# WZ4827R043-ESP32-V1_1-20230705.net
KiCad netlist of a schematic drawn in EAGLE
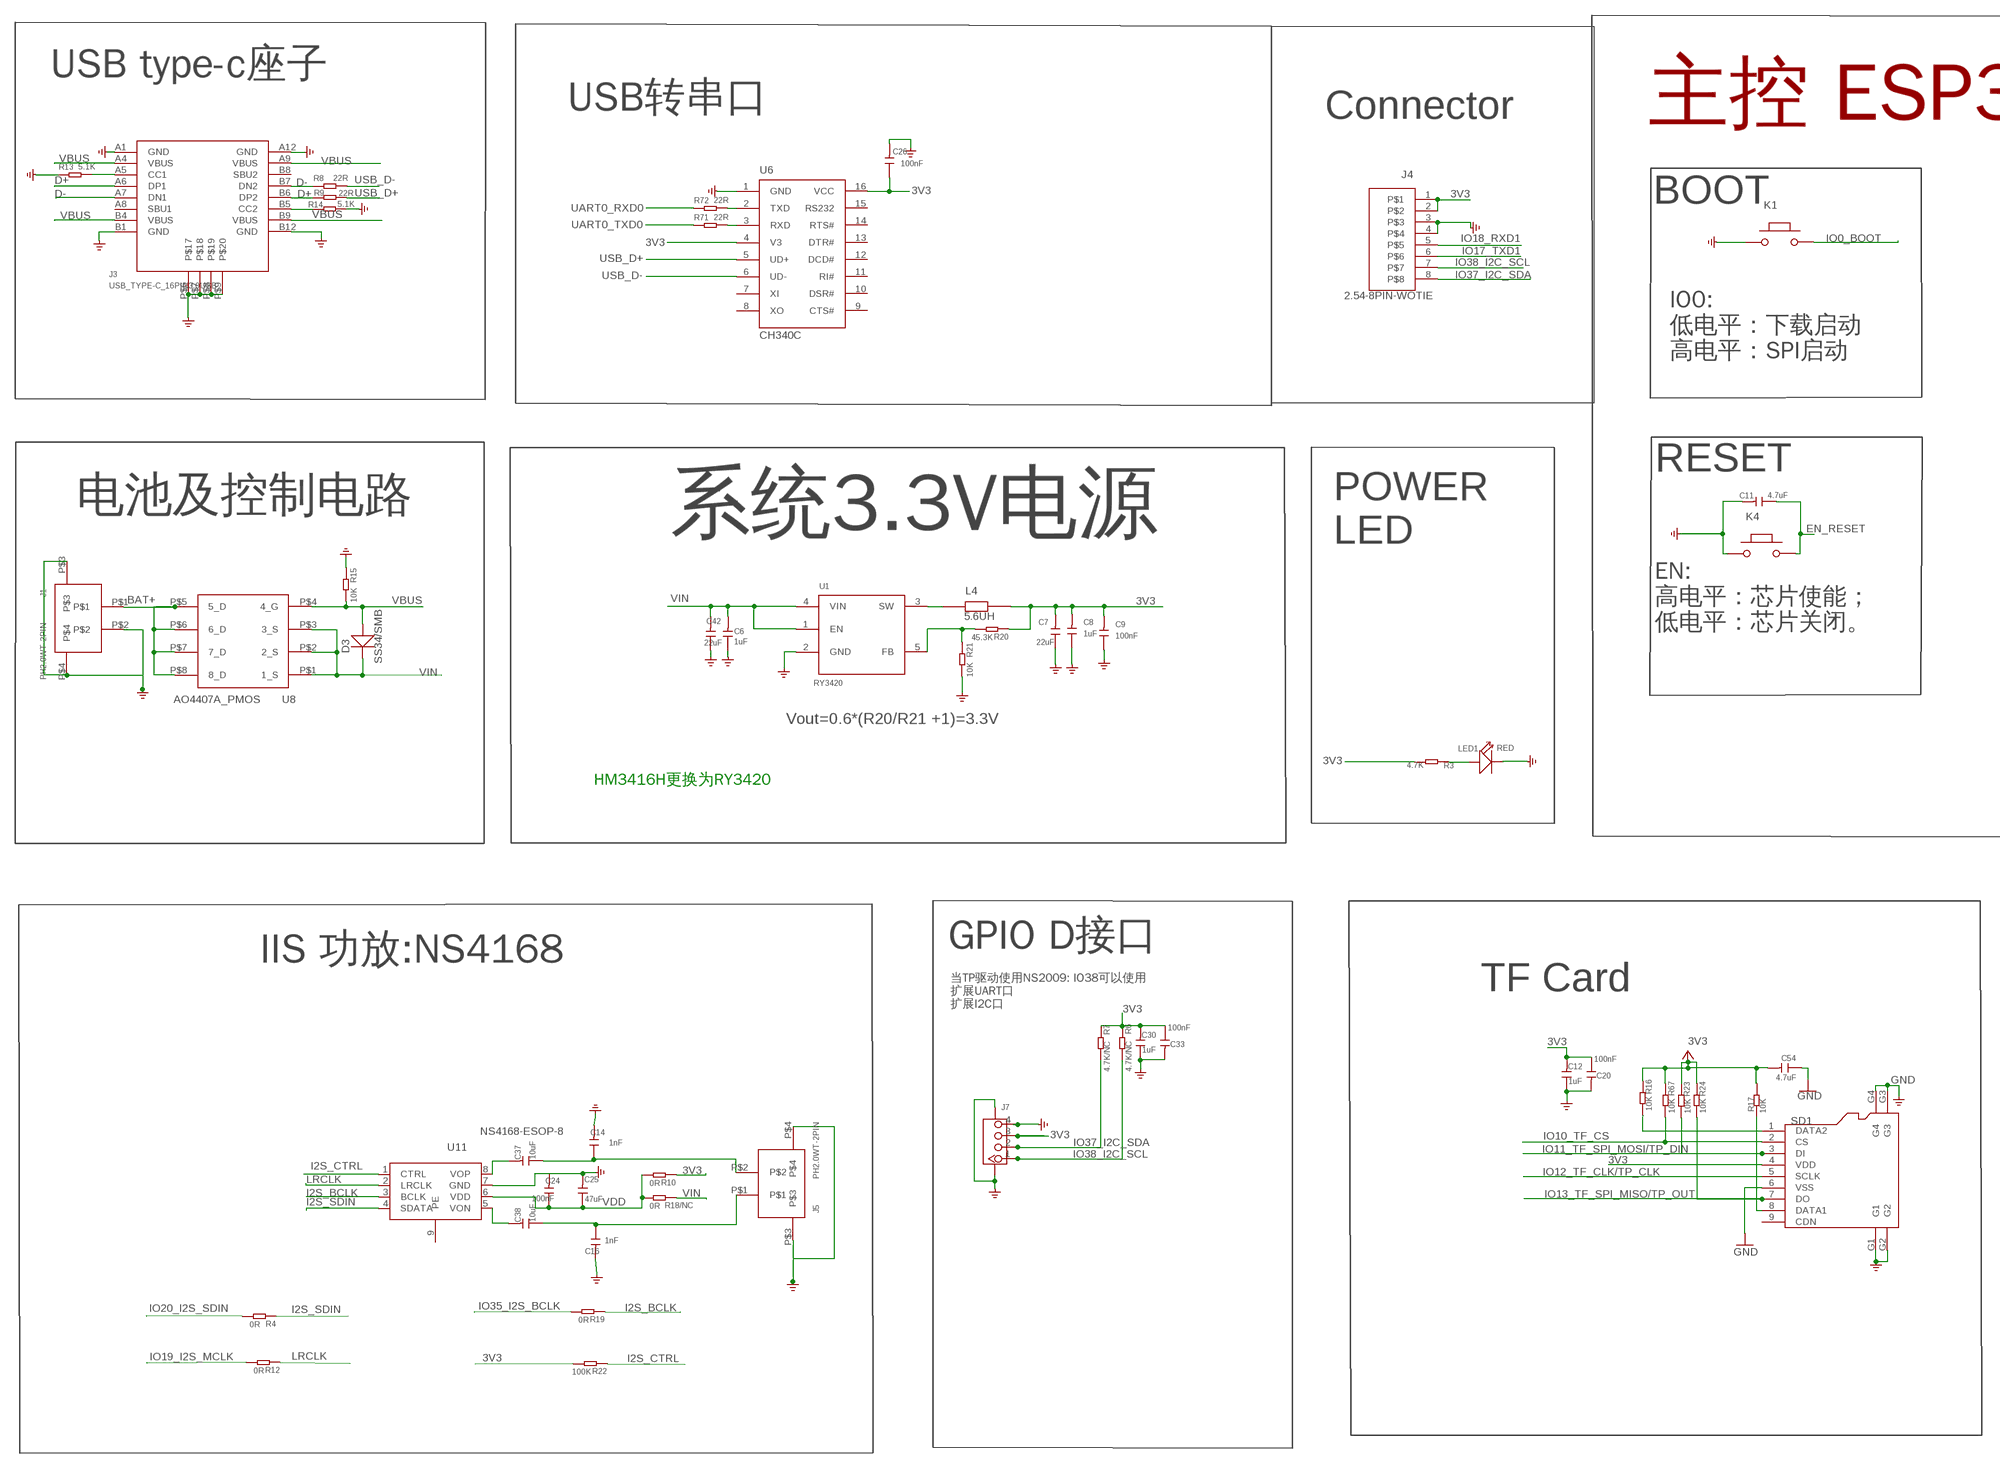
[diagram p0: schematic, sheet 1, part 1 of 2]
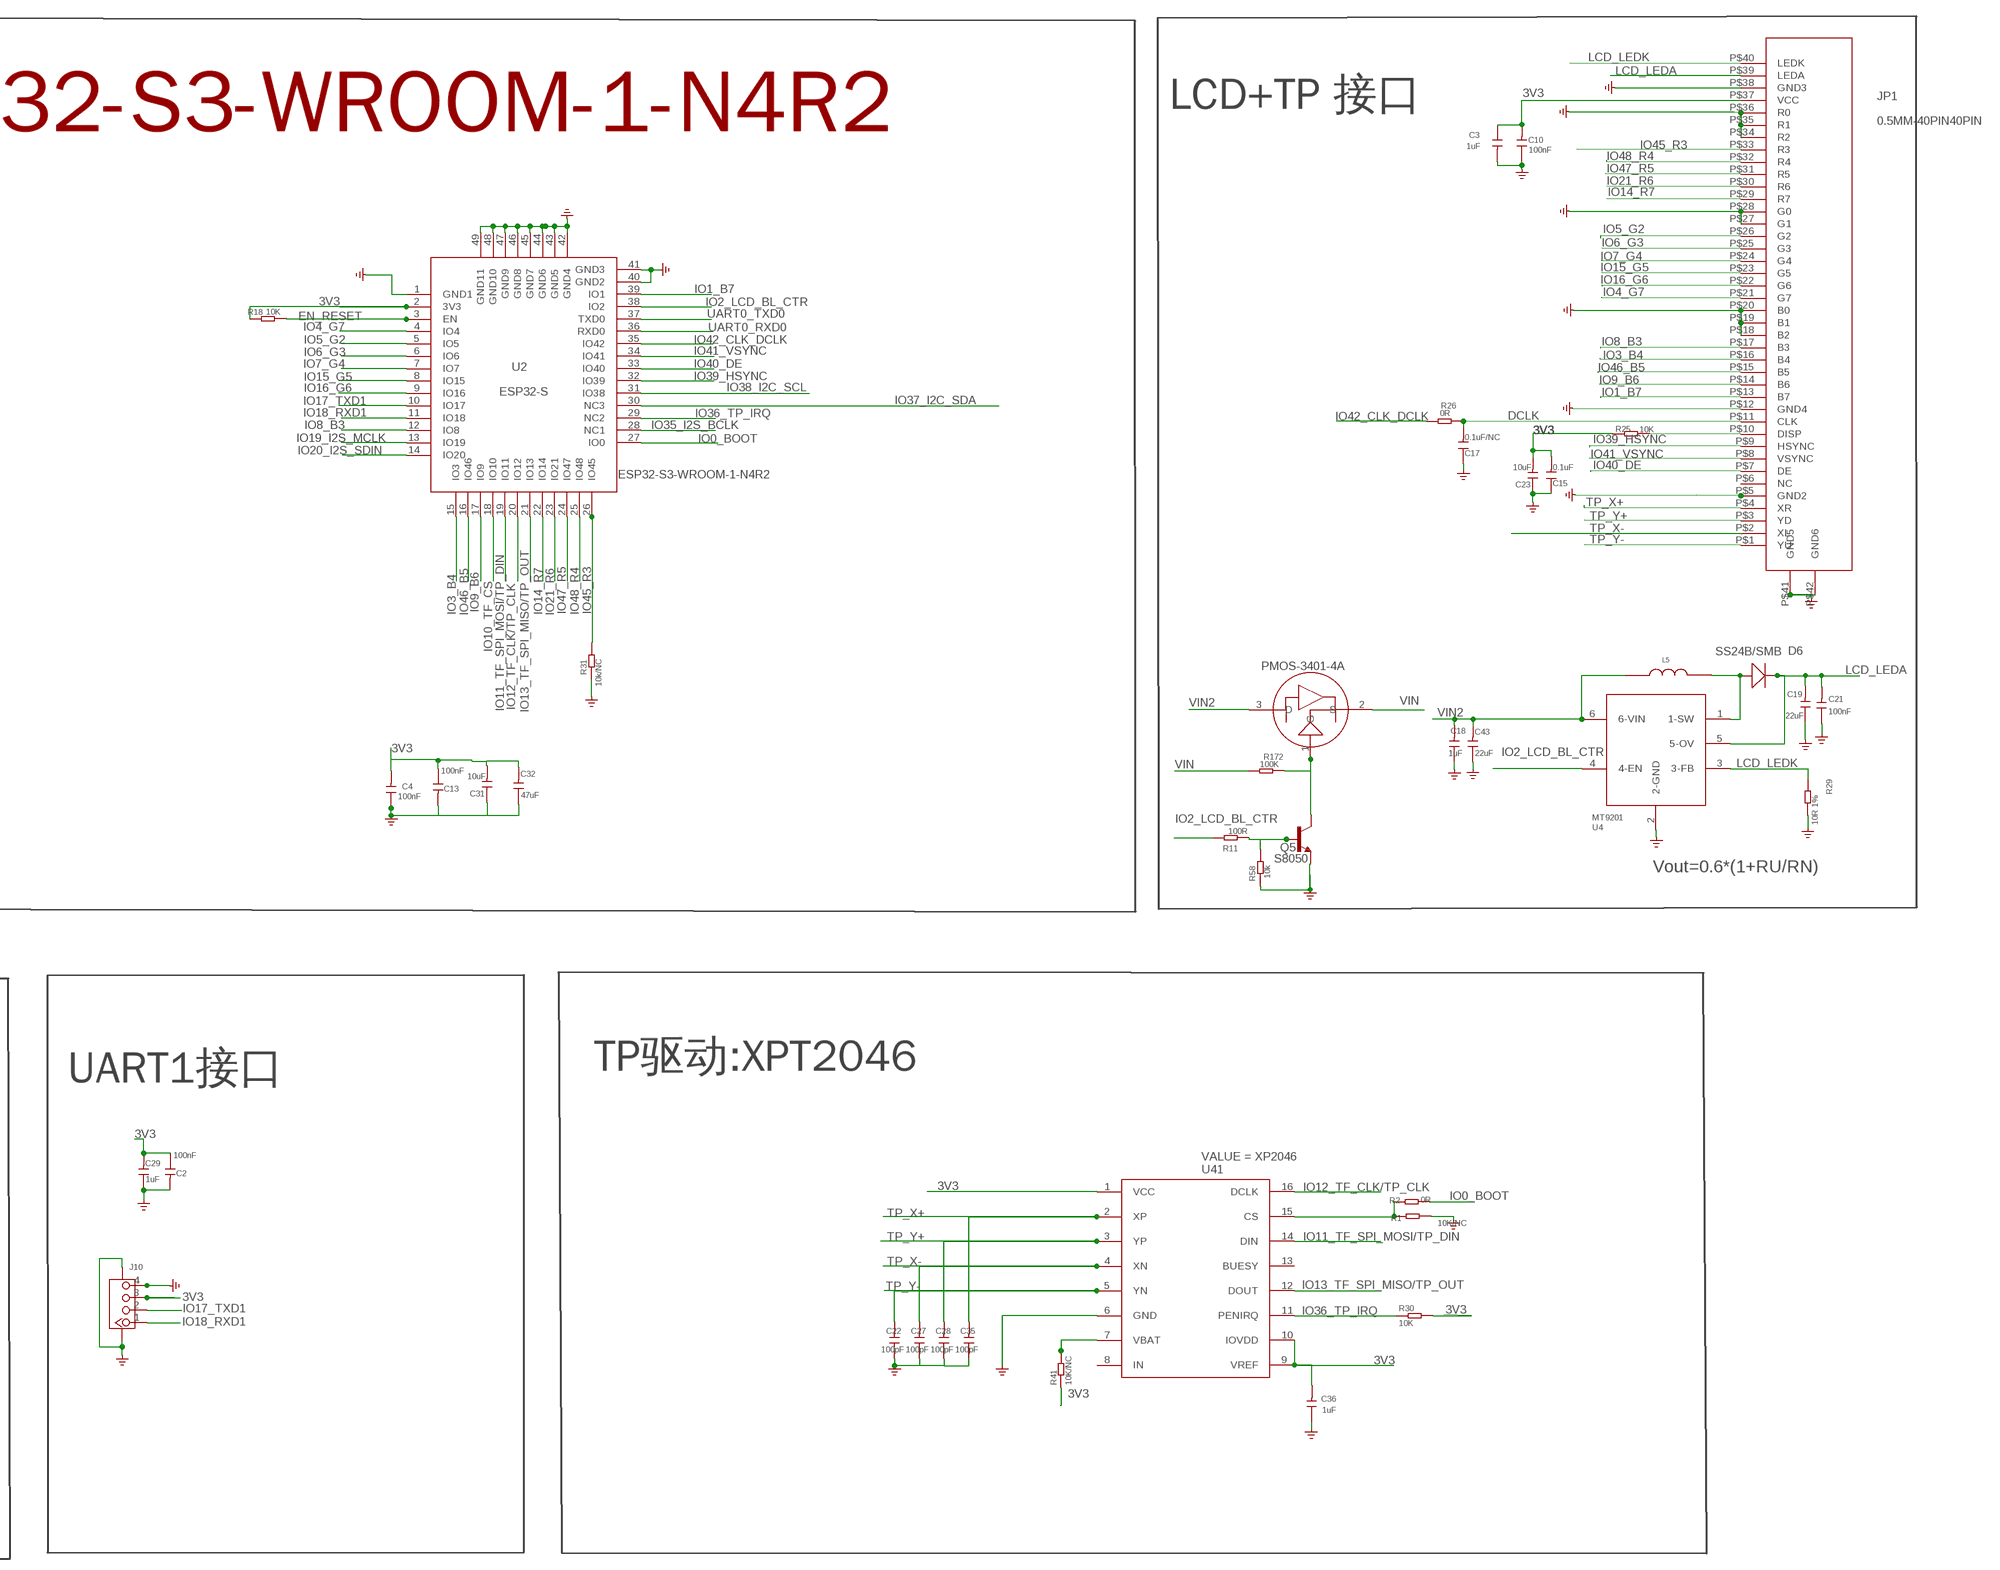
[diagram p1: schematic, sheet 1, part 2 of 2]

(export (version "E")
  (design (tool "Eeschema 10.0.6"))
  (components
    (comp (ref "C2")
      (value "100nF")
      (footprint "eagle-import:C0603")
      (libsource (lib "eagle-import") (part "C-0603"))
    )
    (comp (ref "C3")
      (value "1uF")
      (footprint "eagle-import:C0603")
      (libsource (lib "eagle-import") (part "C-0603"))
    )
    (comp (ref "C4")
      (value "100nF")
      (footprint "eagle-import:C0603")
      (libsource (lib "eagle-import") (part "C-0603"))
    )
    (comp (ref "C6")
      (value "1uF")
      (footprint "eagle-import:0603")
      (libsource (lib "eagle-import") (part "C0603"))
    )
    (comp (ref "C7")
      (value "22uF")
      (footprint "eagle-import:0805")
      (libsource (lib "eagle-import") (part "C0805"))
    )
    (comp (ref "C8")
      (value "1uF")
      (footprint "eagle-import:0603")
      (libsource (lib "eagle-import") (part "C0603"))
    )
    (comp (ref "C9")
      (value "100nF")
      (footprint "eagle-import:0603")
      (libsource (lib "eagle-import") (part "C0603"))
    )
    (comp (ref "C10")
      (value "100nF")
      (footprint "eagle-import:C0603")
      (libsource (lib "eagle-import") (part "C-0603"))
    )
    (comp (ref "C11")
      (value "4.7uF")
      (footprint "eagle-import:0603")
      (libsource (lib "eagle-import") (part "C0603"))
    )
    (comp (ref "C12")
      (value "1uF")
      (footprint "eagle-import:DISCRETE_C0603")
      (libsource (lib "eagle-import") (part "A_xbj_DISCRETE_C-0603"))
    )
    (comp (ref "C13")
      (value "100nF")
      (footprint "eagle-import:C0603")
      (libsource (lib "eagle-import") (part "C-0603"))
    )
    (comp (ref "C14")
      (value "1nF")
      (footprint "eagle-import:C0603")
      (libsource (lib "eagle-import") (part "C-0603"))
    )
    (comp (ref "C15")
      (value "0.1uF")
      (footprint "eagle-import:DISCRETE_C0603")
      (libsource (lib "eagle-import") (part "DISCRETE_C-0603"))
    )
    (comp (ref "C16")
      (value "1nF")
      (footprint "eagle-import:C0603")
      (libsource (lib "eagle-import") (part "C-0603"))
    )
    (comp (ref "C17")
      (value "0.1uF/NC")
      (footprint "eagle-import:DISCRETE_C0603")
      (libsource (lib "eagle-import") (part "DISCRETE_C-0603"))
    )
    (comp (ref "C18")
      (value "1uF")
      (footprint "eagle-import:0603")
      (libsource (lib "eagle-import") (part "C0603"))
    )
    (comp (ref "C19")
      (value "22uF")
      (footprint "eagle-import:0805")
      (libsource (lib "eagle-import") (part "C0805"))
    )
    (comp (ref "C20")
      (value "100nF")
      (footprint "eagle-import:C0603")
      (libsource (lib "eagle-import") (part "C-0603"))
    )
    (comp (ref "C21")
      (value "100nF")
      (footprint "eagle-import:0603")
      (libsource (lib "eagle-import") (part "C0603"))
    )
    (comp (ref "C22")
      (value "100pF")
      (footprint "eagle-import:0603")
      (libsource (lib "eagle-import") (part "C0603"))
    )
    (comp (ref "C23")
      (value "10uF")
      (footprint "eagle-import:DISCRETE_C0603")
      (libsource (lib "eagle-import") (part "DISCRETE_C-0603"))
    )
    (comp (ref "C24")
      (value "100nF")
      (footprint "eagle-import:C0603")
      (libsource (lib "eagle-import") (part "C-0603"))
    )
    (comp (ref "C25")
      (value "47uF")
      (footprint "eagle-import:0805")
      (libsource (lib "eagle-import") (part "C0805"))
    )
    (comp (ref "C26")
      (value "100nF")
      (footprint "eagle-import:0603")
      (libsource (lib "eagle-import") (part "C0603"))
    )
    (comp (ref "C27")
      (value "100pF")
      (footprint "eagle-import:0603")
      (libsource (lib "eagle-import") (part "C0603"))
    )
    (comp (ref "C28")
      (value "100pF")
      (footprint "eagle-import:0603")
      (libsource (lib "eagle-import") (part "C0603"))
    )
    (comp (ref "C29")
      (value "1uF")
      (footprint "eagle-import:DISCRETE_C0603")
      (libsource (lib "eagle-import") (part "A_xbj_DISCRETE_C-0603"))
    )
    (comp (ref "C30")
      (value "1uF")
      (footprint "eagle-import:DISCRETE_C0603")
      (libsource (lib "eagle-import") (part "A_xbj_DISCRETE_C-0603"))
    )
    (comp (ref "C31")
      (value "10uF")
      (footprint "eagle-import:DISCRETE_C0603")
      (libsource (lib "eagle-import") (part "DISCRETE_C-0603"))
    )
    (comp (ref "C32")
      (value "47uF")
      (footprint "eagle-import:0805")
      (libsource (lib "eagle-import") (part "C0805"))
    )
    (comp (ref "C33")
      (value "100nF")
      (footprint "eagle-import:C0603")
      (libsource (lib "eagle-import") (part "C-0603"))
    )
    (comp (ref "C35")
      (value "100pF")
      (footprint "eagle-import:0603")
      (libsource (lib "eagle-import") (part "C0603"))
    )
    (comp (ref "C36")
      (value "1uF")
      (footprint "eagle-import:DISCRETE_C0603")
      (libsource (lib "eagle-import") (part "A_xbj_DISCRETE_C-0603"))
    )
    (comp (ref "C37")
      (value "10uF")
      (footprint "eagle-import:DISCRETE_C0603")
      (libsource (lib "eagle-import") (part "A_xbj_DISCRETE_C-0603"))
    )
    (comp (ref "C38")
      (value "10uF")
      (footprint "eagle-import:DISCRETE_C0603")
      (libsource (lib "eagle-import") (part "A_xbj_DISCRETE_C-0603"))
    )
    (comp (ref "C42")
      (value "22uF")
      (footprint "eagle-import:0805")
      (libsource (lib "eagle-import") (part "C0805"))
    )
    (comp (ref "C43")
      (value "22uF")
      (footprint "eagle-import:0805")
      (libsource (lib "eagle-import") (part "C0805"))
    )
    (comp (ref "C54")
      (value "4.7uF")
      (footprint "eagle-import:DISCRETE_C0603")
      (libsource (lib "eagle-import") (part "DISCRETE_C-0603"))
    )
    (comp (ref "D3")
      (value "SS34/SMB")
      (footprint "eagle-import:214AB")
      (libsource (lib "eagle-import") (part "214ABDO-214AB"))
    )
    (comp (ref "D6")
      (value "SS24B/SMB")
      (footprint "eagle-import:214AB")
      (libsource (lib "eagle-import") (part "214ABDO-214AB"))
    )
    (comp (ref "J1")
      (value "PH2.0WT-2PIN")
      (footprint "eagle-import:PH2.0WT-2PIN")
      (libsource (lib "eagle-import") (part "PH2.0WT-2PIN"))
    )
    (comp (ref "J3")
      (value "USB_TYPE-C_16PIN3.0USB")
      (footprint "eagle-import:KEVIN_3.0TYPEC-SMD")
      (libsource (lib "eagle-import") (part "USB_TYPE-C_16PIN3.0USB"))
    )
    (comp (ref "J4")
      (value "2.54-8PIN-WOTIE")
      (footprint "eagle-import:2.54-8P-WOTIE")
      (libsource (lib "eagle-import") (part "2.54-8PIN-WOTIE"))
    )
    (comp (ref "J5")
      (value "PH2.0WT-2PIN")
      (footprint "eagle-import:PH2.0WT-2PIN")
      (libsource (lib "eagle-import") (part "PH2.0WT-2PIN"))
    )
    (comp (ref "J7")
      (value "CONNECTOR_TWIG-4P-2.0-SMD-FEMALE-REINFORCE90D")
      (footprint "eagle-import:CONNECTOR_4P-SMD-2.0-90D")
      (libsource (lib "eagle-import") (part "CONNECTOR_TWIG-4P-2.0-SMD-FEMALE-REINFORCE90D"))
    )
    (comp (ref "J10")
      (value "CONNECTOR_TWIG-4P-2.0-SMD-FEMALE-REINFORCE90D")
      (footprint "eagle-import:CONNECTOR_4P-SMD-2.0-90D")
      (libsource (lib "eagle-import") (part "CONNECTOR_TWIG-4P-2.0-SMD-FEMALE-REINFORCE90D"))
    )
    (comp (ref "JP1")
      (value "0.5MM-40PIN40PIN")
      (footprint "eagle-import:0.5MM_40P")
      (libsource (lib "eagle-import") (part "0.5MM-40PIN40PIN"))
    )
    (comp (ref "K1")
      (value "BUTTON")
      (footprint "eagle-import:157SW")
      (libsource (lib "eagle-import") (part "PB157"))
    )
    (comp (ref "K4")
      (value "BUTTON")
      (footprint "eagle-import:157SW")
      (libsource (lib "eagle-import") (part "PB157"))
    )
    (comp (ref "L4")
      (value "5.6UH")
      (footprint "eagle-import:CD54")
      (libsource (lib "eagle-import") (part "CROWPI2-MB-V1.4-20211012_CMP201209UD1R0MT"))
    )
    (comp (ref "L5")
      (value "CD32_6.8uH")
      (footprint "eagle-import:CD32")
      (libsource (lib "eagle-import") (part "CD32_950MA"))
    )
    (comp (ref "LED1")
      (value "RED")
      (footprint "eagle-import:DISCRETE_LED-0603")
      (libsource (lib "eagle-import") (part "DISCRETE_LED0603"))
    )
    (comp (ref "Q5")
      (value "S8050")
      (footprint "eagle-import:SPARKFUN_SOT23")
      (libsource (lib "eagle-import") (part "SPARKFUN_TRANSISTOR_NPNSOT23"))
    )
    (comp (ref "Q30")
      (value "PMOS-3401-4A")
      (footprint "eagle-import:SOT-23")
      (libsource (lib "eagle-import") (part "P-MOS-SOT23"))
    )
    (comp (ref "R1")
      (value "10K/NC")
      (footprint "eagle-import:R0603")
      (libsource (lib "eagle-import") (part "R0603"))
    )
    (comp (ref "R2")
      (value "0R")
      (footprint "eagle-import:DISCRETE_R0603")
      (libsource (lib "eagle-import") (part "Crowtail-_LED-V2.0-20190615-01_DISCRETE_R-0603"))
    )
    (comp (ref "R3")
      (value "4.7K")
      (footprint "eagle-import:DISCRETE_R0603")
      (libsource (lib "eagle-import") (part "Crowtail-_LED-V2.0-20190615-01_DISCRETE_R-0603"))
    )
    (comp (ref "R4")
      (value "0R")
      (footprint "eagle-import:DISCRETE_R0603")
      (libsource (lib "eagle-import") (part "Crowtail-_LED-V2.0-20190615-01_DISCRETE_R-0603"))
    )
    (comp (ref "R6")
      (value "4.7K/NC")
      (footprint "eagle-import:DISCRETE_R0603")
      (libsource (lib "eagle-import") (part "Crowtail-_LED-V2.0-20190615-01_DISCRETE_R-0603"))
    )
    (comp (ref "R7")
      (value "4.7K/NC")
      (footprint "eagle-import:DISCRETE_R0603")
      (libsource (lib "eagle-import") (part "Crowtail-_LED-V2.0-20190615-01_DISCRETE_R-0603"))
    )
    (comp (ref "R8")
      (value "22R")
      (footprint "eagle-import:DISCRETE_R0603")
      (libsource (lib "eagle-import") (part "Crowtail-_LED-V2.0-20190615-01_DISCRETE_R-0603"))
    )
    (comp (ref "R9")
      (value "22R")
      (footprint "eagle-import:DISCRETE_R0603")
      (libsource (lib "eagle-import") (part "Crowtail-_LED-V2.0-20190615-01_DISCRETE_R-0603"))
    )
    (comp (ref "R10")
      (value "0R")
      (footprint "eagle-import:DISCRETE_R0603")
      (libsource (lib "eagle-import") (part "Crowtail-_LED-V2.0-20190615-01_DISCRETE_R-0603"))
    )
    (comp (ref "R11")
      (value "100R")
      (footprint "eagle-import:R0603")
      (libsource (lib "eagle-import") (part "R0603"))
    )
    (comp (ref "R12")
      (value "0R")
      (footprint "eagle-import:DISCRETE_R0603")
      (libsource (lib "eagle-import") (part "Crowtail-_LED-V2.0-20190615-01_DISCRETE_R-0603"))
    )
    (comp (ref "R13")
      (value "5.1K")
      (footprint "eagle-import:DISCRETE_R0603")
      (libsource (lib "eagle-import") (part "Crowtail-_LED-V2.0-20190615-01_DISCRETE_R-0603"))
    )
    (comp (ref "R14")
      (value "5.1K")
      (footprint "eagle-import:DISCRETE_R0603")
      (libsource (lib "eagle-import") (part "Crowtail-_LED-V2.0-20190615-01_DISCRETE_R-0603"))
    )
    (comp (ref "R15")
      (value "10K")
      (footprint "eagle-import:DISCRETE_R0603")
      (libsource (lib "eagle-import") (part "Crowtail-_LED-V2.0-20190615-01_DISCRETE_R-0603"))
    )
    (comp (ref "R16")
      (value "10K")
      (footprint "eagle-import:DISCRETE_R0603")
      (libsource (lib "eagle-import") (part "Crowtail-_LED-V2.0-20190615-01_DISCRETE_R-0603"))
    )
    (comp (ref "R17")
      (value "10K")
      (footprint "eagle-import:DISCRETE_R0603")
      (libsource (lib "eagle-import") (part "Crowtail-_LED-V2.0-20190615-01_DISCRETE_R-0603"))
    )
    (comp (ref "R18")
      (value "10K")
      (footprint "eagle-import:DISCRETE_R0603")
      (libsource (lib "eagle-import") (part "Crowtail-_LED-V2.0-20190615-01_DISCRETE_R-0603"))
    )
    (comp (ref "R18/NC")
      (value "0R")
      (footprint "eagle-import:DISCRETE_R0603")
      (libsource (lib "eagle-import") (part "Crowtail-_LED-V2.0-20190615-01_DISCRETE_R-0603"))
    )
    (comp (ref "R19")
      (value "0R")
      (footprint "eagle-import:DISCRETE_R0603")
      (libsource (lib "eagle-import") (part "Crowtail-_LED-V2.0-20190615-01_DISCRETE_R-0603"))
    )
    (comp (ref "R20")
      (value "45.3K")
      (footprint "eagle-import:DISCRETE_R0603")
      (libsource (lib "eagle-import") (part "Crowtail-_LED-V2.0-20190615-01_DISCRETE_R-0603"))
    )
    (comp (ref "R21")
      (value "10K")
      (footprint "eagle-import:DISCRETE_R0603")
      (libsource (lib "eagle-import") (part "Crowtail-_LED-V2.0-20190615-01_DISCRETE_R-0603"))
    )
    (comp (ref "R22")
      (value "100K")
      (footprint "eagle-import:DISCRETE_R0603")
      (libsource (lib "eagle-import") (part "Crowtail-_LED-V2.0-20190615-01_DISCRETE_R-0603"))
    )
    (comp (ref "R23")
      (value "10K")
      (footprint "eagle-import:DISCRETE_R0603")
      (libsource (lib "eagle-import") (part "Crowtail-_LED-V2.0-20190615-01_DISCRETE_R-0603"))
    )
    (comp (ref "R24")
      (value "10K")
      (footprint "eagle-import:DISCRETE_R0603")
      (libsource (lib "eagle-import") (part "Crowtail-_LED-V2.0-20190615-01_DISCRETE_R-0603"))
    )
    (comp (ref "R25")
      (value "10K")
      (footprint "eagle-import:DISCRETE_R0603")
      (libsource (lib "eagle-import") (part "Crowtail-_LED-V2.0-20190615-01_DISCRETE_R-0603"))
    )
    (comp (ref "R26")
      (value "0R")
      (footprint "eagle-import:R0603")
      (libsource (lib "eagle-import") (part "R-0603"))
    )
    (comp (ref "R29")
      (value "10R 1%")
      (footprint "eagle-import:DISCRETE_R0603")
      (libsource (lib "eagle-import") (part "Crowtail-_LED-V2.0-20190615-01_DISCRETE_R-0603"))
    )
    (comp (ref "R30")
      (value "10K")
      (footprint "eagle-import:DISCRETE_R0603")
      (libsource (lib "eagle-import") (part "DISCRETE_R-0603"))
    )
    (comp (ref "R31")
      (value "10k/NC")
      (footprint "eagle-import:R0603")
      (libsource (lib "eagle-import") (part "R0603"))
    )
    (comp (ref "R41")
      (value "10K/NC")
      (footprint "eagle-import:DISCRETE_R0603")
      (libsource (lib "eagle-import") (part "DISCRETE_R-0603"))
    )
    (comp (ref "R58")
      (value "10k")
      (footprint "eagle-import:R0603")
      (libsource (lib "eagle-import") (part "R0603"))
    )
    (comp (ref "R67")
      (value "10K")
      (footprint "eagle-import:DISCRETE_R0603")
      (libsource (lib "eagle-import") (part "Crowtail-_LED-V2.0-20190615-01_DISCRETE_R-0603"))
    )
    (comp (ref "R71")
      (value "22R")
      (footprint "eagle-import:DISCRETE_R0603")
      (libsource (lib "eagle-import") (part "Crowtail-_LED-V2.0-20190615-01_DISCRETE_R-0603"))
    )
    (comp (ref "R72")
      (value "22R")
      (footprint "eagle-import:DISCRETE_R0603")
      (libsource (lib "eagle-import") (part "Crowtail-_LED-V2.0-20190615-01_DISCRETE_R-0603"))
    )
    (comp (ref "R172")
      (value "100K")
      (footprint "eagle-import:R0603")
      (libsource (lib "eagle-import") (part "R-0603"))
    )
    (comp (ref "SD1")
      (value "HOLDER-MICROSD-9P")
      (footprint "eagle-import:9P-SMD-W_-RING")
      (libsource (lib "eagle-import") (part "HOLDER-MICROSD-9P"))
    )
    (comp (ref "U1")
      (value "RY3420")
      (footprint "eagle-import:A_XBJ_SOT23-5")
      (libsource (lib "eagle-import") (part "A_XBJ_HM3420B"))
    )
    (comp (ref "U2")
      (value "ESP32-S")
      (footprint "eagle-import:ESP32-S3")
      (fields (field (name "U2") "ESP32-S3-WROOM-1-N4R2"))
      (libsource (lib "eagle-import") (part "ESP32-S"))
    )
    (comp (ref "U4")
      (value "MT9201")
      (footprint "eagle-import:SOT23-6")
      (libsource (lib "eagle-import") (part "MT9201"))
    )
    (comp (ref "U6")
      (value "CH340C")
      (footprint "eagle-import:SOP-16")
      (libsource (lib "eagle-import") (part "CH340G"))
    )
    (comp (ref "U8")
      (value "AO4407A_PMOS")
      (footprint "eagle-import:SOP8")
      (libsource (lib "eagle-import") (part "T_PMOS_AO4407A_SOP8"))
    )
    (comp (ref "U11")
      (value "NS4168-ESOP-8")
      (footprint "eagle-import:NS4168-ESOP-8")
      (libsource (lib "eagle-import") (part "NS4168-ESOP-8"))
    )
    (comp (ref "U41")
      (value "XP2046")
      (footprint "eagle-import:XP2046-SSOP16")
      (libsource (lib "eagle-import") (part "XP2046"))
    )
  )
  (nets
    (net (code "1") (name "+3V3") (class "Default")
      (node (ref "C10") (pin "2") (pinfunction "2_2") (pintype "passive"))
      (node (ref "C12") (pin "2") (pinfunction "2_2") (pintype "passive"))
      (node (ref "C13") (pin "1") (pinfunction "1_1") (pintype "passive"))
      (node (ref "C15") (pin "2") (pinfunction "2_2") (pintype "passive"))
      (node (ref "C2") (pin "1") (pinfunction "1_1") (pintype "passive"))
      (node (ref "C20") (pin "1") (pinfunction "1_1") (pintype "passive"))
      (node (ref "C23") (pin "2") (pinfunction "2_2") (pintype "passive"))
      (node (ref "C26") (pin "1") (pinfunction "1_1") (pintype "passive"))
      (node (ref "C29") (pin "2") (pinfunction "2_2") (pintype "passive"))
      (node (ref "C3") (pin "1") (pinfunction "1_1") (pintype "passive"))
      (node (ref "C30") (pin "2") (pinfunction "2_2") (pintype "passive"))
      (node (ref "C31") (pin "2") (pinfunction "2_2") (pintype "passive"))
      (node (ref "C32") (pin "2") (pinfunction "2_2") (pintype "passive"))
      (node (ref "C33") (pin "1") (pinfunction "1_1") (pintype "passive"))
      (node (ref "C36") (pin "2") (pinfunction "2_2") (pintype "passive"))
      (node (ref "C4") (pin "2") (pinfunction "2_2") (pintype "passive"))
      (node (ref "C54") (pin "2") (pinfunction "2_2") (pintype "passive"))
      (node (ref "C7") (pin "2") (pinfunction "2_2") (pintype "passive"))
      (node (ref "C8") (pin "2") (pinfunction "2_2") (pintype "passive"))
      (node (ref "C9") (pin "2") (pinfunction "2_2") (pintype "passive"))
      (node (ref "J10") (pin "3") (pinfunction "3_3") (pintype "bidirectional"))
      (node (ref "J4") (pin "1") (pinfunction "P$1_1") (pintype "bidirectional"))
      (node (ref "J4") (pin "2") (pinfunction "P$2_2") (pintype "bidirectional"))
      (node (ref "J7") (pin "3") (pinfunction "3_3") (pintype "bidirectional"))
      (node (ref "JP1") (pin "P$37") (pinfunction "VCC_P$37") (pintype "bidirectional"))
      (node (ref "L4") (pin "2") (pinfunction "2_2") (pintype "bidirectional"))
      (node (ref "R10") (pin "1") (pinfunction "1_1") (pintype "passive"))
      (node (ref "R16") (pin "1") (pinfunction "1_1") (pintype "passive"))
      (node (ref "R17") (pin "1") (pinfunction "1_1") (pintype "passive"))
      (node (ref "R18") (pin "1") (pinfunction "1_1") (pintype "passive"))
      (node (ref "R20") (pin "1") (pinfunction "1_1") (pintype "passive"))
      (node (ref "R22") (pin "2") (pinfunction "2_2") (pintype "passive"))
      (node (ref "R23") (pin "1") (pinfunction "1_1") (pintype "passive"))
      (node (ref "R24") (pin "1") (pinfunction "1_1") (pintype "passive"))
      (node (ref "R25") (pin "1") (pinfunction "1_1") (pintype "passive"))
      (node (ref "R3") (pin "2") (pinfunction "2_2") (pintype "passive"))
      (node (ref "R30") (pin "2") (pinfunction "2_2") (pintype "passive"))
      (node (ref "R41") (pin "1") (pinfunction "1_1") (pintype "passive"))
      (node (ref "R6") (pin "1") (pinfunction "1_1") (pintype "passive"))
      (node (ref "R67") (pin "1") (pinfunction "1_1") (pintype "passive"))
      (node (ref "R7") (pin "1") (pinfunction "1_1") (pintype "passive"))
      (node (ref "SD1") (pin "4") (pinfunction "VDD_4") (pintype "bidirectional"))
      (node (ref "U2") (pin "2") (pinfunction "3V3_2") (pintype "bidirectional"))
      (node (ref "U41") (pin "1") (pinfunction "VCC_1") (pintype "bidirectional"))
      (node (ref "U41") (pin "10") (pinfunction "IOVDD_10") (pintype "bidirectional"))
      (node (ref "U41") (pin "9") (pinfunction "VREF_9") (pintype "bidirectional"))
      (node (ref "U6") (pin "16") (pinfunction "VCC_16") (pintype "bidirectional"))
      (node (ref "U6") (pin "4") (pinfunction "V3_4") (pintype "bidirectional"))
    )
    (net (code "2") (name "/BAT+") (class "Default")
      (node (ref "J1") (pin "P$1") (pinfunction "P$1_P$1") (pintype "bidirectional"))
      (node (ref "U8") (pin "P$5") (pinfunction "5_D_P$5") (pintype "bidirectional"))
      (node (ref "U8") (pin "P$6") (pinfunction "6_D_P$6") (pintype "bidirectional"))
      (node (ref "U8") (pin "P$7") (pinfunction "7_D_P$7") (pintype "bidirectional"))
      (node (ref "U8") (pin "P$8") (pinfunction "8_D_P$8") (pintype "bidirectional"))
    )
    (net (code "3") (name "/D+") (class "Default")
      (node (ref "J3") (pin "A6") (pinfunction "DP1_A6") (pintype "bidirectional"))
      (node (ref "J3") (pin "B6") (pinfunction "DP2_B6") (pintype "bidirectional"))
      (node (ref "R9") (pin "1") (pinfunction "1_1") (pintype "passive"))
    )
    (net (code "4") (name "/D-") (class "Default")
      (node (ref "J3") (pin "A7") (pinfunction "DN1_A7") (pintype "bidirectional"))
      (node (ref "J3") (pin "B7") (pinfunction "DN2_B7") (pintype "bidirectional"))
      (node (ref "R8") (pin "1") (pinfunction "1_1") (pintype "passive"))
    )
    (net (code "5") (name "/DCLK") (class "Default")
      (node (ref "C17") (pin "2") (pinfunction "2_2") (pintype "passive"))
      (node (ref "JP1") (pin "P$11") (pinfunction "CLK_P$11") (pintype "bidirectional"))
      (node (ref "R26") (pin "2") (pinfunction "2_2") (pintype "passive"))
    )
    (net (code "6") (name "/EN_RESET") (class "Default")
      (node (ref "C11") (pin "1") (pinfunction "1_1") (pintype "passive"))
      (node (ref "K4") (pin "2") (pinfunction "2_2") (pintype "passive"))
      (node (ref "R18") (pin "2") (pinfunction "2_2") (pintype "passive"))
      (node (ref "U2") (pin "3") (pinfunction "EN_3") (pintype "bidirectional"))
    )
    (net (code "7") (name "/I2S_BCLK") (class "Default")
      (node (ref "R19") (pin "1") (pinfunction "1_1") (pintype "passive"))
      (node (ref "U11") (pin "3") (pinfunction "BCLK_3") (pintype "bidirectional"))
    )
    (net (code "8") (name "/I2S_CTRL") (class "Default")
      (node (ref "R22") (pin "1") (pinfunction "1_1") (pintype "passive"))
      (node (ref "U11") (pin "1") (pinfunction "CTRL_1") (pintype "bidirectional"))
    )
    (net (code "9") (name "/I2S_SDIN") (class "Default")
      (node (ref "R4") (pin "1") (pinfunction "1_1") (pintype "passive"))
      (node (ref "U11") (pin "4") (pinfunction "SDATA_4") (pintype "bidirectional"))
    )
    (net (code "10") (name "/IO0_BOOT") (class "Default")
      (node (ref "K1") (pin "2") (pinfunction "2_2") (pintype "passive"))
      (node (ref "R2") (pin "1") (pinfunction "1_1") (pintype "passive"))
      (node (ref "U2") (pin "27") (pinfunction "IO0_27") (pintype "bidirectional"))
    )
    (net (code "11") (name "/IO1_B7") (class "Default")
      (node (ref "JP1") (pin "P$13") (pinfunction "B7_P$13") (pintype "bidirectional"))
      (node (ref "U2") (pin "39") (pinfunction "IO1_39") (pintype "bidirectional"))
    )
    (net (code "12") (name "/IO2_LCD_BL_CTR") (class "Default")
      (node (ref "R11") (pin "2") (pinfunction "2_2") (pintype "passive"))
      (node (ref "U2") (pin "38") (pinfunction "IO2_38") (pintype "bidirectional"))
      (node (ref "U4") (pin "4") (pinfunction "4-EN_4") (pintype "bidirectional"))
    )
    (net (code "13") (name "/IO3_B4") (class "Default")
      (node (ref "JP1") (pin "P$16") (pinfunction "B4_P$16") (pintype "bidirectional"))
      (node (ref "U2") (pin "15") (pinfunction "IO3_15") (pintype "bidirectional"))
    )
    (net (code "14") (name "/IO4_G7") (class "Default")
      (node (ref "JP1") (pin "P$21") (pinfunction "G7_P$21") (pintype "bidirectional"))
      (node (ref "U2") (pin "4") (pinfunction "IO4_4") (pintype "bidirectional"))
    )
    (net (code "15") (name "/IO5_G2") (class "Default")
      (node (ref "JP1") (pin "P$26") (pinfunction "G2_P$26") (pintype "bidirectional"))
      (node (ref "U2") (pin "5") (pinfunction "IO5_5") (pintype "bidirectional"))
    )
    (net (code "16") (name "/IO6_G3") (class "Default")
      (node (ref "JP1") (pin "P$25") (pinfunction "G3_P$25") (pintype "bidirectional"))
      (node (ref "U2") (pin "6") (pinfunction "IO6_6") (pintype "bidirectional"))
    )
    (net (code "17") (name "/IO7_G4") (class "Default")
      (node (ref "JP1") (pin "P$24") (pinfunction "G4_P$24") (pintype "bidirectional"))
      (node (ref "U2") (pin "7") (pinfunction "IO7_7") (pintype "bidirectional"))
    )
    (net (code "18") (name "/IO8_B3") (class "Default")
      (node (ref "JP1") (pin "P$17") (pinfunction "B3_P$17") (pintype "bidirectional"))
      (node (ref "U2") (pin "12") (pinfunction "IO8_12") (pintype "bidirectional"))
    )
    (net (code "19") (name "/IO9_B6") (class "Default")
      (node (ref "JP1") (pin "P$14") (pinfunction "B6_P$14") (pintype "bidirectional"))
      (node (ref "U2") (pin "17") (pinfunction "IO9_17") (pintype "bidirectional"))
    )
    (net (code "20") (name "/IO10_TF_CS") (class "Default")
      (node (ref "R67") (pin "2") (pinfunction "2_2") (pintype "passive"))
      (node (ref "SD1") (pin "2") (pinfunction "CS_2") (pintype "bidirectional"))
      (node (ref "U2") (pin "18") (pinfunction "IO10_18") (pintype "bidirectional"))
    )
    (net (code "21") (name "/IO11_TF_SPI_MOSI{slash}TP_DIN") (class "Default")
      (node (ref "R23") (pin "2") (pinfunction "2_2") (pintype "passive"))
      (node (ref "SD1") (pin "3") (pinfunction "DI_3") (pintype "bidirectional"))
      (node (ref "U2") (pin "19") (pinfunction "IO11_19") (pintype "bidirectional"))
      (node (ref "U41") (pin "14") (pinfunction "DIN_14") (pintype "bidirectional"))
    )
    (net (code "22") (name "/IO12_TF_CLK{slash}TP_CLK") (class "Default")
      (node (ref "SD1") (pin "5") (pinfunction "SCLK_5") (pintype "bidirectional"))
      (node (ref "U2") (pin "20") (pinfunction "IO12_20") (pintype "bidirectional"))
      (node (ref "U41") (pin "16") (pinfunction "DCLK_16") (pintype "bidirectional"))
    )
    (net (code "23") (name "/IO13_TF_SPI_MISO{slash}TP_OUT") (class "Default")
      (node (ref "R24") (pin "2") (pinfunction "2_2") (pintype "passive"))
      (node (ref "SD1") (pin "7") (pinfunction "DO_7") (pintype "bidirectional"))
      (node (ref "U2") (pin "21") (pinfunction "IO13_21") (pintype "bidirectional"))
      (node (ref "U41") (pin "12") (pinfunction "DOUT_12") (pintype "bidirectional"))
    )
    (net (code "24") (name "/IO14_R7") (class "Default")
      (node (ref "JP1") (pin "P$29") (pinfunction "R7_P$29") (pintype "bidirectional"))
      (node (ref "U2") (pin "22") (pinfunction "IO14_22") (pintype "bidirectional"))
    )
    (net (code "25") (name "/IO15_G5") (class "Default")
      (node (ref "JP1") (pin "P$23") (pinfunction "G5_P$23") (pintype "bidirectional"))
      (node (ref "U2") (pin "8") (pinfunction "IO15_8") (pintype "bidirectional"))
    )
    (net (code "26") (name "/IO16_G6") (class "Default")
      (node (ref "JP1") (pin "P$22") (pinfunction "G6_P$22") (pintype "bidirectional"))
      (node (ref "U2") (pin "9") (pinfunction "IO16_9") (pintype "bidirectional"))
    )
    (net (code "27") (name "/IO17_TXD1") (class "Default")
      (node (ref "J10") (pin "2") (pinfunction "2_2") (pintype "bidirectional"))
      (node (ref "J4") (pin "6") (pinfunction "P$6_6") (pintype "bidirectional"))
      (node (ref "U2") (pin "10") (pinfunction "IO17_10") (pintype "bidirectional"))
    )
    (net (code "28") (name "/IO18_RXD1") (class "Default")
      (node (ref "J10") (pin "1") (pinfunction "1_1") (pintype "bidirectional"))
      (node (ref "J4") (pin "5") (pinfunction "P$5_5") (pintype "bidirectional"))
      (node (ref "U2") (pin "11") (pinfunction "IO18_11") (pintype "bidirectional"))
    )
    (net (code "29") (name "/IO19_I2S_MCLK") (class "Default")
      (node (ref "R12") (pin "2") (pinfunction "2_2") (pintype "passive"))
      (node (ref "U2") (pin "13") (pinfunction "IO19_13") (pintype "bidirectional"))
    )
    (net (code "30") (name "/IO20_I2S_SDIN") (class "Default")
      (node (ref "R4") (pin "2") (pinfunction "2_2") (pintype "passive"))
      (node (ref "U2") (pin "14") (pinfunction "IO20_14") (pintype "bidirectional"))
    )
    (net (code "31") (name "/IO21_R6") (class "Default")
      (node (ref "JP1") (pin "P$30") (pinfunction "R6_P$30") (pintype "bidirectional"))
      (node (ref "U2") (pin "23") (pinfunction "IO21_23") (pintype "bidirectional"))
    )
    (net (code "32") (name "/IO35_I2S_BCLK") (class "Default")
      (node (ref "R19") (pin "2") (pinfunction "2_2") (pintype "passive"))
      (node (ref "U2") (pin "28") (pinfunction "NC1_28") (pintype "bidirectional"))
    )
    (net (code "33") (name "/IO36_TP_IRQ") (class "Default")
      (node (ref "R30") (pin "1") (pinfunction "1_1") (pintype "passive"))
      (node (ref "U2") (pin "29") (pinfunction "NC2_29") (pintype "bidirectional"))
      (node (ref "U41") (pin "11") (pinfunction "PENIRQ_11") (pintype "bidirectional"))
    )
    (net (code "34") (name "/IO37_I2C_SDA") (class "Default")
      (node (ref "J4") (pin "8") (pinfunction "P$8_8") (pintype "bidirectional"))
      (node (ref "J7") (pin "2") (pinfunction "2_2") (pintype "bidirectional"))
      (node (ref "R7") (pin "2") (pinfunction "2_2") (pintype "passive"))
      (node (ref "U2") (pin "30") (pinfunction "NC3_30") (pintype "bidirectional"))
    )
    (net (code "35") (name "/IO38_I2C_SCL") (class "Default")
      (node (ref "J4") (pin "7") (pinfunction "P$7_7") (pintype "bidirectional"))
      (node (ref "J7") (pin "1") (pinfunction "1_1") (pintype "bidirectional"))
      (node (ref "R6") (pin "2") (pinfunction "2_2") (pintype "passive"))
      (node (ref "U2") (pin "31") (pinfunction "IO38_31") (pintype "bidirectional"))
    )
    (net (code "36") (name "/IO39_HSYNC") (class "Default")
      (node (ref "JP1") (pin "P$9") (pinfunction "HSYNC_P$9") (pintype "bidirectional"))
      (node (ref "U2") (pin "32") (pinfunction "IO39_32") (pintype "bidirectional"))
    )
    (net (code "37") (name "/IO40_DE") (class "Default")
      (node (ref "JP1") (pin "P$7") (pinfunction "DE_P$7") (pintype "bidirectional"))
      (node (ref "U2") (pin "33") (pinfunction "IO40_33") (pintype "bidirectional"))
    )
    (net (code "38") (name "/IO41_VSYNC") (class "Default")
      (node (ref "JP1") (pin "P$8") (pinfunction "VSYNC_P$8") (pintype "bidirectional"))
      (node (ref "U2") (pin "34") (pinfunction "IO41_34") (pintype "bidirectional"))
    )
    (net (code "39") (name "/IO42_CLK_DCLK") (class "Default")
      (node (ref "R26") (pin "1") (pinfunction "1_1") (pintype "passive"))
      (node (ref "U2") (pin "35") (pinfunction "IO42_35") (pintype "bidirectional"))
    )
    (net (code "40") (name "/IO45_R3") (class "Default")
      (node (ref "JP1") (pin "P$33") (pinfunction "R3_P$33") (pintype "bidirectional"))
      (node (ref "R31") (pin "2") (pinfunction "2_2") (pintype "passive"))
      (node (ref "U2") (pin "26") (pinfunction "IO45_26") (pintype "bidirectional"))
    )
    (net (code "41") (name "/IO46_B5") (class "Default")
      (node (ref "JP1") (pin "P$15") (pinfunction "B5_P$15") (pintype "bidirectional"))
      (node (ref "U2") (pin "16") (pinfunction "IO46_16") (pintype "bidirectional"))
    )
    (net (code "42") (name "/IO47_R5") (class "Default")
      (node (ref "JP1") (pin "P$31") (pinfunction "R5_P$31") (pintype "bidirectional"))
      (node (ref "U2") (pin "24") (pinfunction "IO47_24") (pintype "bidirectional"))
    )
    (net (code "43") (name "/IO48_R4") (class "Default")
      (node (ref "JP1") (pin "P$32") (pinfunction "R4_P$32") (pintype "bidirectional"))
      (node (ref "U2") (pin "25") (pinfunction "IO48_25") (pintype "bidirectional"))
    )
    (net (code "44") (name "/LCD_LEDA") (class "Default")
      (node (ref "C19") (pin "2") (pinfunction "2_2") (pintype "passive"))
      (node (ref "C21") (pin "2") (pinfunction "2_2") (pintype "passive"))
      (node (ref "D6") (pin "2") (pinfunction "-_2") (pintype "passive"))
      (node (ref "JP1") (pin "P$39") (pinfunction "LEDA_P$39") (pintype "bidirectional"))
      (node (ref "U4") (pin "5") (pinfunction "5-OV_5") (pintype "bidirectional"))
    )
    (net (code "45") (name "/LCD_LEDK") (class "Default")
      (node (ref "JP1") (pin "P$40") (pinfunction "LEDK_P$40") (pintype "bidirectional"))
      (node (ref "R29") (pin "1") (pinfunction "1_1") (pintype "passive"))
      (node (ref "U4") (pin "3") (pinfunction "3-FB_3") (pintype "bidirectional"))
    )
    (net (code "46") (name "/LRCLK") (class "Default")
      (node (ref "R12") (pin "1") (pinfunction "1_1") (pintype "passive"))
      (node (ref "U11") (pin "2") (pinfunction "LRCLK_2") (pintype "bidirectional"))
    )
    (net (code "47") (name "/TP_X+") (class "Default")
      (node (ref "C35") (pin "2") (pinfunction "2_2") (pintype "passive"))
      (node (ref "JP1") (pin "P$4") (pinfunction "XR_P$4") (pintype "bidirectional"))
      (node (ref "U41") (pin "2") (pinfunction "XP_2") (pintype "bidirectional"))
    )
    (net (code "48") (name "/TP_X-") (class "Default")
      (node (ref "C27") (pin "2") (pinfunction "2_2") (pintype "passive"))
      (node (ref "JP1") (pin "P$2") (pinfunction "XL_P$2") (pintype "bidirectional"))
      (node (ref "U41") (pin "4") (pinfunction "XN_4") (pintype "bidirectional"))
    )
    (net (code "49") (name "/TP_Y+") (class "Default")
      (node (ref "C28") (pin "2") (pinfunction "2_2") (pintype "passive"))
      (node (ref "JP1") (pin "P$3") (pinfunction "YD_P$3") (pintype "bidirectional"))
      (node (ref "U41") (pin "3") (pinfunction "YP_3") (pintype "bidirectional"))
    )
    (net (code "50") (name "/TP_Y-") (class "Default")
      (node (ref "C22") (pin "2") (pinfunction "2_2") (pintype "passive"))
      (node (ref "JP1") (pin "P$1") (pinfunction "YU_P$1") (pintype "bidirectional"))
      (node (ref "U41") (pin "5") (pinfunction "YN_5") (pintype "bidirectional"))
    )
    (net (code "51") (name "/UART0_RXD0") (class "Default")
      (node (ref "R72") (pin "1") (pinfunction "1_1") (pintype "passive"))
      (node (ref "U2") (pin "36") (pinfunction "RXD0_36") (pintype "bidirectional"))
    )
    (net (code "52") (name "/UART0_TXD0") (class "Default")
      (node (ref "R71") (pin "1") (pinfunction "1_1") (pintype "passive"))
      (node (ref "U2") (pin "37") (pinfunction "TXD0_37") (pintype "bidirectional"))
    )
    (net (code "53") (name "/USB_D+") (class "Default")
      (node (ref "R9") (pin "2") (pinfunction "2_2") (pintype "passive"))
      (node (ref "U6") (pin "5") (pinfunction "UD+_5") (pintype "bidirectional"))
    )
    (net (code "54") (name "/USB_D-") (class "Default")
      (node (ref "R8") (pin "2") (pinfunction "2_2") (pintype "passive"))
      (node (ref "U6") (pin "6") (pinfunction "UD-_6") (pintype "bidirectional"))
    )
    (net (code "55") (name "/VBUS") (class "Default")
      (node (ref "D3") (pin "1") (pinfunction "+_1") (pintype "passive"))
      (node (ref "J3") (pin "A4") (pinfunction "VBUS_A4") (pintype "bidirectional"))
      (node (ref "J3") (pin "A9") (pinfunction "VBUS_A9") (pintype "bidirectional"))
      (node (ref "J3") (pin "B4") (pinfunction "VBUS_B4") (pintype "bidirectional"))
      (node (ref "J3") (pin "B9") (pinfunction "VBUS_B9") (pintype "bidirectional"))
      (node (ref "R15") (pin "2") (pinfunction "2_2") (pintype "passive"))
      (node (ref "U8") (pin "P$4") (pinfunction "4_G_P$4") (pintype "bidirectional"))
    )
    (net (code "56") (name "/VDD") (class "Default")
      (node (ref "C24") (pin "1") (pinfunction "1_1") (pintype "passive"))
      (node (ref "C25") (pin "1") (pinfunction "1_1") (pintype "passive"))
      (node (ref "R10") (pin "2") (pinfunction "2_2") (pintype "passive"))
      (node (ref "R18/NC") (pin "2") (pinfunction "2_2") (pintype "passive"))
      (node (ref "U11") (pin "6") (pinfunction "VDD_6") (pintype "bidirectional"))
    )
    (net (code "57") (name "/VIN") (class "Default")
      (node (ref "C42") (pin "2") (pinfunction "2_2") (pintype "passive"))
      (node (ref "C6") (pin "2") (pinfunction "2_2") (pintype "passive"))
      (node (ref "D3") (pin "2") (pinfunction "-_2") (pintype "passive"))
      (node (ref "Q30") (pin "2") (pinfunction "S_2") (pintype "bidirectional"))
      (node (ref "R172") (pin "1") (pinfunction "1_1") (pintype "passive"))
      (node (ref "R18/NC") (pin "1") (pinfunction "1_1") (pintype "passive"))
      (node (ref "U1") (pin "1") (pinfunction "EN_1") (pintype "bidirectional"))
      (node (ref "U1") (pin "4") (pinfunction "VIN_4") (pintype "bidirectional"))
      (node (ref "U8") (pin "P$1") (pinfunction "1_S_P$1") (pintype "bidirectional"))
      (node (ref "U8") (pin "P$2") (pinfunction "2_S_P$2") (pintype "bidirectional"))
      (node (ref "U8") (pin "P$3") (pinfunction "3_S_P$3") (pintype "bidirectional"))
    )
    (net (code "58") (name "/VIN2") (class "Default")
      (node (ref "C18") (pin "2") (pinfunction "2_2") (pintype "passive"))
      (node (ref "C43") (pin "2") (pinfunction "2_2") (pintype "passive"))
      (node (ref "L5") (pin "1") (pinfunction "1_1") (pintype "bidirectional"))
      (node (ref "Q30") (pin "3") (pinfunction "D_3") (pintype "bidirectional"))
      (node (ref "U4") (pin "6") (pinfunction "6-VIN_6") (pintype "bidirectional"))
    )
    (net (code "59") (name "GND") (class "Default")
      (node (ref "C10") (pin "1") (pinfunction "1_1") (pintype "passive"))
      (node (ref "C11") (pin "2") (pinfunction "2_2") (pintype "passive"))
      (node (ref "C12") (pin "1") (pinfunction "1_1") (pintype "passive"))
      (node (ref "C13") (pin "2") (pinfunction "2_2") (pintype "passive"))
      (node (ref "C14") (pin "2") (pinfunction "2_2") (pintype "passive"))
      (node (ref "C15") (pin "1") (pinfunction "1_1") (pintype "passive"))
      (node (ref "C16") (pin "2") (pinfunction "2_2") (pintype "passive"))
      (node (ref "C17") (pin "1") (pinfunction "1_1") (pintype "passive"))
      (node (ref "C18") (pin "1") (pinfunction "1_1") (pintype "passive"))
      (node (ref "C19") (pin "1") (pinfunction "1_1") (pintype "passive"))
      (node (ref "C2") (pin "2") (pinfunction "2_2") (pintype "passive"))
      (node (ref "C20") (pin "2") (pinfunction "2_2") (pintype "passive"))
      (node (ref "C21") (pin "1") (pinfunction "1_1") (pintype "passive"))
      (node (ref "C22") (pin "1") (pinfunction "1_1") (pintype "passive"))
      (node (ref "C23") (pin "1") (pinfunction "1_1") (pintype "passive"))
      (node (ref "C24") (pin "2") (pinfunction "2_2") (pintype "passive"))
      (node (ref "C25") (pin "2") (pinfunction "2_2") (pintype "passive"))
      (node (ref "C26") (pin "2") (pinfunction "2_2") (pintype "passive"))
      (node (ref "C27") (pin "1") (pinfunction "1_1") (pintype "passive"))
      (node (ref "C28") (pin "1") (pinfunction "1_1") (pintype "passive"))
      (node (ref "C29") (pin "1") (pinfunction "1_1") (pintype "passive"))
      (node (ref "C3") (pin "2") (pinfunction "2_2") (pintype "passive"))
      (node (ref "C30") (pin "1") (pinfunction "1_1") (pintype "passive"))
      (node (ref "C31") (pin "1") (pinfunction "1_1") (pintype "passive"))
      (node (ref "C32") (pin "1") (pinfunction "1_1") (pintype "passive"))
      (node (ref "C33") (pin "2") (pinfunction "2_2") (pintype "passive"))
      (node (ref "C35") (pin "1") (pinfunction "1_1") (pintype "passive"))
      (node (ref "C36") (pin "1") (pinfunction "1_1") (pintype "passive"))
      (node (ref "C4") (pin "1") (pinfunction "1_1") (pintype "passive"))
      (node (ref "C42") (pin "1") (pinfunction "1_1") (pintype "passive"))
      (node (ref "C43") (pin "1") (pinfunction "1_1") (pintype "passive"))
      (node (ref "C54") (pin "1") (pinfunction "1_1") (pintype "passive"))
      (node (ref "C6") (pin "1") (pinfunction "1_1") (pintype "passive"))
      (node (ref "C7") (pin "1") (pinfunction "1_1") (pintype "passive"))
      (node (ref "C8") (pin "1") (pinfunction "1_1") (pintype "passive"))
      (node (ref "C9") (pin "1") (pinfunction "1_1") (pintype "passive"))
      (node (ref "J1") (pin "P$2") (pinfunction "P$2_P$2") (pintype "bidirectional"))
      (node (ref "J1") (pin "P$3") (pinfunction "P$3_P$3") (pintype "bidirectional"))
      (node (ref "J1") (pin "P$4") (pinfunction "P$4_P$4") (pintype "bidirectional"))
      (node (ref "J10") (pin "4") (pinfunction "4_4") (pintype "bidirectional"))
      (node (ref "J10") (pin "SS1") (pinfunction "SS1_SS1") (pintype "bidirectional"))
      (node (ref "J10") (pin "SS2") (pinfunction "SS2_SS2") (pintype "bidirectional"))
      (node (ref "J3") (pin "A1") (pinfunction "GND_A1") (pintype "bidirectional"))
      (node (ref "J3") (pin "A12") (pinfunction "GND_A12") (pintype "bidirectional"))
      (node (ref "J3") (pin "B1") (pinfunction "GND_B1") (pintype "bidirectional"))
      (node (ref "J3") (pin "B12") (pinfunction "GND_B12") (pintype "bidirectional"))
      (node (ref "J3") (pin "P$6") (pinfunction "P$17_P$6") (pintype "bidirectional"))
      (node (ref "J3") (pin "P$7") (pinfunction "P$18_P$7") (pintype "bidirectional"))
      (node (ref "J3") (pin "P$8") (pinfunction "P$19_P$8") (pintype "bidirectional"))
      (node (ref "J3") (pin "P$9") (pinfunction "P$20_P$9") (pintype "bidirectional"))
      (node (ref "J4") (pin "3") (pinfunction "P$3_3") (pintype "bidirectional"))
      (node (ref "J4") (pin "4") (pinfunction "P$4_4") (pintype "bidirectional"))
      (node (ref "J5") (pin "P$3") (pinfunction "P$3_P$3") (pintype "bidirectional"))
      (node (ref "J5") (pin "P$4") (pinfunction "P$4_P$4") (pintype "bidirectional"))
      (node (ref "J7") (pin "4") (pinfunction "4_4") (pintype "bidirectional"))
      (node (ref "J7") (pin "SS1") (pinfunction "SS1_SS1") (pintype "bidirectional"))
      (node (ref "J7") (pin "SS2") (pinfunction "SS2_SS2") (pintype "bidirectional"))
      (node (ref "JP1") (pin "P$12") (pinfunction "GND4_P$12") (pintype "bidirectional"))
      (node (ref "JP1") (pin "P$18") (pinfunction "B2_P$18") (pintype "bidirectional"))
      (node (ref "JP1") (pin "P$19") (pinfunction "B1_P$19") (pintype "bidirectional"))
      (node (ref "JP1") (pin "P$20") (pinfunction "B0_P$20") (pintype "bidirectional"))
      (node (ref "JP1") (pin "P$27") (pinfunction "G1_P$27") (pintype "bidirectional"))
      (node (ref "JP1") (pin "P$28") (pinfunction "G0_P$28") (pintype "bidirectional"))
      (node (ref "JP1") (pin "P$34") (pinfunction "R2_P$34") (pintype "bidirectional"))
      (node (ref "JP1") (pin "P$35") (pinfunction "R1_P$35") (pintype "bidirectional"))
      (node (ref "JP1") (pin "P$36") (pinfunction "R0_P$36") (pintype "bidirectional"))
      (node (ref "JP1") (pin "P$38") (pinfunction "GND3_P$38") (pintype "bidirectional"))
      (node (ref "JP1") (pin "P$41") (pinfunction "GND5_P$41") (pintype "bidirectional"))
      (node (ref "JP1") (pin "P$42") (pinfunction "GND6_P$42") (pintype "bidirectional"))
      (node (ref "JP1") (pin "P$5") (pinfunction "GND2_P$5") (pintype "bidirectional"))
      (node (ref "K1") (pin "1") (pinfunction "1_1") (pintype "passive"))
      (node (ref "K4") (pin "1") (pinfunction "1_1") (pintype "passive"))
      (node (ref "LED1") (pin "-") (pinfunction "-_-") (pintype "passive"))
      (node (ref "Q5") (pin "2") (pinfunction "E_2") (pintype "passive"))
      (node (ref "R1") (pin "1") (pinfunction "1_1") (pintype "passive"))
      (node (ref "R13") (pin "1") (pinfunction "1_1") (pintype "passive"))
      (node (ref "R14") (pin "2") (pinfunction "2_2") (pintype "passive"))
      (node (ref "R15") (pin "1") (pinfunction "1_1") (pintype "passive"))
      (node (ref "R21") (pin "2") (pinfunction "2_2") (pintype "passive"))
      (node (ref "R29") (pin "2") (pinfunction "2_2") (pintype "passive"))
      (node (ref "R31") (pin "1") (pinfunction "1_1") (pintype "passive"))
      (node (ref "R58") (pin "1") (pinfunction "1_1") (pintype "passive"))
      (node (ref "SD1") (pin "6") (pinfunction "VSS_6") (pintype "bidirectional"))
      (node (ref "SD1") (pin "G1") (pinfunction "G1_G1") (pintype "bidirectional"))
      (node (ref "SD1") (pin "G2") (pinfunction "G2_G2") (pintype "bidirectional"))
      (node (ref "SD1") (pin "G3") (pinfunction "G3_G3") (pintype "bidirectional"))
      (node (ref "SD1") (pin "G4") (pinfunction "G4_G4") (pintype "bidirectional"))
      (node (ref "U1") (pin "2") (pinfunction "GND_2") (pintype "bidirectional"))
      (node (ref "U11") (pin "7") (pinfunction "GND_7") (pintype "bidirectional"))
      (node (ref "U2") (pin "1") (pinfunction "GND1_1") (pintype "bidirectional"))
      (node (ref "U2") (pin "40") (pinfunction "GND2_40") (pintype "bidirectional"))
      (node (ref "U2") (pin "41") (pinfunction "GND3_41") (pintype "bidirectional"))
      (node (ref "U2") (pin "42") (pinfunction "GND4_42") (pintype "bidirectional"))
      (node (ref "U2") (pin "43") (pinfunction "GND5_43") (pintype "bidirectional"))
      (node (ref "U2") (pin "44") (pinfunction "GND6_44") (pintype "bidirectional"))
      (node (ref "U2") (pin "45") (pinfunction "GND7_45") (pintype "bidirectional"))
      (node (ref "U2") (pin "46") (pinfunction "GND8_46") (pintype "bidirectional"))
      (node (ref "U2") (pin "47") (pinfunction "GND9_47") (pintype "bidirectional"))
      (node (ref "U2") (pin "48") (pinfunction "GND10_48") (pintype "bidirectional"))
      (node (ref "U2") (pin "49") (pinfunction "GND11_49") (pintype "bidirectional"))
      (node (ref "U4") (pin "2") (pinfunction "2-GND_2") (pintype "bidirectional"))
      (node (ref "U41") (pin "6") (pinfunction "GND_6") (pintype "bidirectional"))
      (node (ref "U6") (pin "1") (pinfunction "GND_1") (pintype "bidirectional"))
    )
    (net (code "60") (name "Net-(C14-Pad1)") (class "Default")
      (node (ref "C14") (pin "1") (pinfunction "1_1") (pintype "passive"))
      (node (ref "C37") (pin "1") (pinfunction "1_1") (pintype "passive"))
      (node (ref "J5") (pin "P$2") (pinfunction "P$2_P$2") (pintype "bidirectional"))
    )
    (net (code "61") (name "Net-(C16-Pad1)") (class "Default")
      (node (ref "C16") (pin "1") (pinfunction "1_1") (pintype "passive"))
      (node (ref "C38") (pin "1") (pinfunction "1_1") (pintype "passive"))
      (node (ref "J5") (pin "P$1") (pinfunction "P$1_P$1") (pintype "bidirectional"))
    )
    (net (code "62") (name "Net-(D6-+)") (class "Default")
      (node (ref "D6") (pin "1") (pinfunction "+_1") (pintype "passive"))
      (node (ref "L5") (pin "2") (pinfunction "2_2") (pintype "bidirectional"))
      (node (ref "U4") (pin "1") (pinfunction "1-SW_1") (pintype "bidirectional"))
    )
    (net (code "63") (name "Net-(J3-CC1)") (class "Default")
      (node (ref "J3") (pin "A5") (pinfunction "CC1_A5") (pintype "bidirectional"))
      (node (ref "R13") (pin "2") (pinfunction "2_2") (pintype "passive"))
    )
    (net (code "64") (name "Net-(J3-CC2)") (class "Default")
      (node (ref "J3") (pin "B5") (pinfunction "CC2_B5") (pintype "bidirectional"))
      (node (ref "R14") (pin "1") (pinfunction "1_1") (pintype "passive"))
    )
    (net (code "65") (name "Net-(JP1-DISP)") (class "Default")
      (node (ref "JP1") (pin "P$10") (pinfunction "DISP_P$10") (pintype "bidirectional"))
      (node (ref "R25") (pin "2") (pinfunction "2_2") (pintype "passive"))
    )
    (net (code "66") (name "Net-(LED1-Pad+)") (class "Default")
      (node (ref "LED1") (pin "+") (pinfunction "+_+") (pintype "passive"))
      (node (ref "R3") (pin "1") (pinfunction "1_1") (pintype "passive"))
    )
    (net (code "67") (name "Net-(Q5-B)") (class "Default")
      (node (ref "Q5") (pin "1") (pinfunction "B_1") (pintype "passive"))
      (node (ref "R11") (pin "1") (pinfunction "1_1") (pintype "passive"))
      (node (ref "R58") (pin "2") (pinfunction "2_2") (pintype "passive"))
    )
    (net (code "68") (name "Net-(Q30-G)") (class "Default")
      (node (ref "Q30") (pin "1") (pinfunction "G_1") (pintype "bidirectional"))
      (node (ref "Q5") (pin "3") (pinfunction "C_3") (pintype "passive"))
      (node (ref "R172") (pin "2") (pinfunction "2_2") (pintype "passive"))
    )
    (net (code "69") (name "Net-(SD1-DATA1)") (class "Default")
      (node (ref "R17") (pin "2") (pinfunction "2_2") (pintype "passive"))
      (node (ref "SD1") (pin "8") (pinfunction "DATA1_8") (pintype "bidirectional"))
    )
    (net (code "70") (name "Net-(SD1-DATA2)") (class "Default")
      (node (ref "R16") (pin "2") (pinfunction "2_2") (pintype "passive"))
      (node (ref "SD1") (pin "1") (pinfunction "DATA2_1") (pintype "bidirectional"))
    )
    (net (code "71") (name "Net-(U1-FB)") (class "Default")
      (node (ref "R20") (pin "2") (pinfunction "2_2") (pintype "passive"))
      (node (ref "R21") (pin "1") (pinfunction "1_1") (pintype "passive"))
      (node (ref "U1") (pin "5") (pinfunction "FB_5") (pintype "bidirectional"))
    )
    (net (code "72") (name "Net-(U1-SW)") (class "Default")
      (node (ref "L4") (pin "1") (pinfunction "1_1") (pintype "bidirectional"))
      (node (ref "U1") (pin "3") (pinfunction "SW_3") (pintype "bidirectional"))
    )
    (net (code "73") (name "Net-(U6-RXD)") (class "Default")
      (node (ref "R71") (pin "2") (pinfunction "2_2") (pintype "passive"))
      (node (ref "U6") (pin "3") (pinfunction "RXD_3") (pintype "bidirectional"))
    )
    (net (code "74") (name "Net-(U6-TXD)") (class "Default")
      (node (ref "R72") (pin "2") (pinfunction "2_2") (pintype "passive"))
      (node (ref "U6") (pin "2") (pinfunction "TXD_2") (pintype "bidirectional"))
    )
    (net (code "75") (name "Net-(U11-VON)") (class "Default")
      (node (ref "C38") (pin "2") (pinfunction "2_2") (pintype "passive"))
      (node (ref "U11") (pin "5") (pinfunction "VON_5") (pintype "bidirectional"))
    )
    (net (code "76") (name "Net-(U11-VOP)") (class "Default")
      (node (ref "C37") (pin "2") (pinfunction "2_2") (pintype "passive"))
      (node (ref "U11") (pin "8") (pinfunction "VOP_8") (pintype "bidirectional"))
    )
    (net (code "77") (name "Net-(U41-CS)") (class "Default")
      (node (ref "R1") (pin "2") (pinfunction "2_2") (pintype "passive"))
      (node (ref "R2") (pin "2") (pinfunction "2_2") (pintype "passive"))
      (node (ref "U41") (pin "15") (pinfunction "CS_15") (pintype "bidirectional"))
    )
    (net (code "78") (name "Net-(U41-VBAT)") (class "Default")
      (node (ref "R41") (pin "2") (pinfunction "2_2") (pintype "passive"))
      (node (ref "U41") (pin "7") (pinfunction "VBAT_7") (pintype "bidirectional"))
    )
    (net (code "79") (name "unconnected-(J3-SBU1-PadA8)") (class "Default")
      (node (ref "J3") (pin "A8") (pinfunction "SBU1_A8") (pintype "bidirectional"))
    )
    (net (code "80") (name "unconnected-(J3-SBU2-PadB8)") (class "Default")
      (node (ref "J3") (pin "B8") (pinfunction "SBU2_B8") (pintype "bidirectional"))
    )
    (net (code "81") (name "unconnected-(JP1-NC-PadP$6)") (class "Default")
      (node (ref "JP1") (pin "P$6") (pinfunction "NC_P$6") (pintype "bidirectional"))
    )
    (net (code "82") (name "unconnected-(SD1-CDN-Pad9)") (class "Default")
      (node (ref "SD1") (pin "9") (pinfunction "CDN_9") (pintype "bidirectional"))
    )
    (net (code "83") (name "unconnected-(U6-CTS#-Pad9)") (class "Default")
      (node (ref "U6") (pin "9") (pinfunction "CTS#_9") (pintype "bidirectional"))
    )
    (net (code "84") (name "unconnected-(U6-DCD#-Pad12)") (class "Default")
      (node (ref "U6") (pin "12") (pinfunction "DCD#_12") (pintype "bidirectional"))
    )
    (net (code "85") (name "unconnected-(U6-DSR#-Pad10)") (class "Default")
      (node (ref "U6") (pin "10") (pinfunction "DSR#_10") (pintype "bidirectional"))
    )
    (net (code "86") (name "unconnected-(U6-DTR#-Pad13)") (class "Default")
      (node (ref "U6") (pin "13") (pinfunction "DTR#_13") (pintype "bidirectional"))
    )
    (net (code "87") (name "unconnected-(U6-RI#-Pad11)") (class "Default")
      (node (ref "U6") (pin "11") (pinfunction "RI#_11") (pintype "bidirectional"))
    )
    (net (code "88") (name "unconnected-(U6-RS232-Pad15)") (class "Default")
      (node (ref "U6") (pin "15") (pinfunction "RS232_15") (pintype "bidirectional"))
    )
    (net (code "89") (name "unconnected-(U6-RTS#-Pad14)") (class "Default")
      (node (ref "U6") (pin "14") (pinfunction "RTS#_14") (pintype "bidirectional"))
    )
    (net (code "90") (name "unconnected-(U6-XI-Pad7)") (class "Default")
      (node (ref "U6") (pin "7") (pinfunction "XI_7") (pintype "bidirectional"))
    )
    (net (code "91") (name "unconnected-(U6-XO-Pad8)") (class "Default")
      (node (ref "U6") (pin "8") (pinfunction "XO_8") (pintype "bidirectional"))
    )
    (net (code "92") (name "unconnected-(U11-PE-Pad9)") (class "Default")
      (node (ref "U11") (pin "9") (pinfunction "PE_9") (pintype "bidirectional"))
    )
    (net (code "93") (name "unconnected-(U41-BUESY-Pad13)") (class "Default")
      (node (ref "U41") (pin "13") (pinfunction "BUESY_13") (pintype "bidirectional"))
    )
    (net (code "94") (name "unconnected-(U41-IN-Pad8)") (class "Default")
      (node (ref "U41") (pin "8") (pinfunction "IN_8") (pintype "bidirectional"))
    )
  )
)
